# dice2_perf.net
KiCad netlist of a schematic drawn in EAGLE
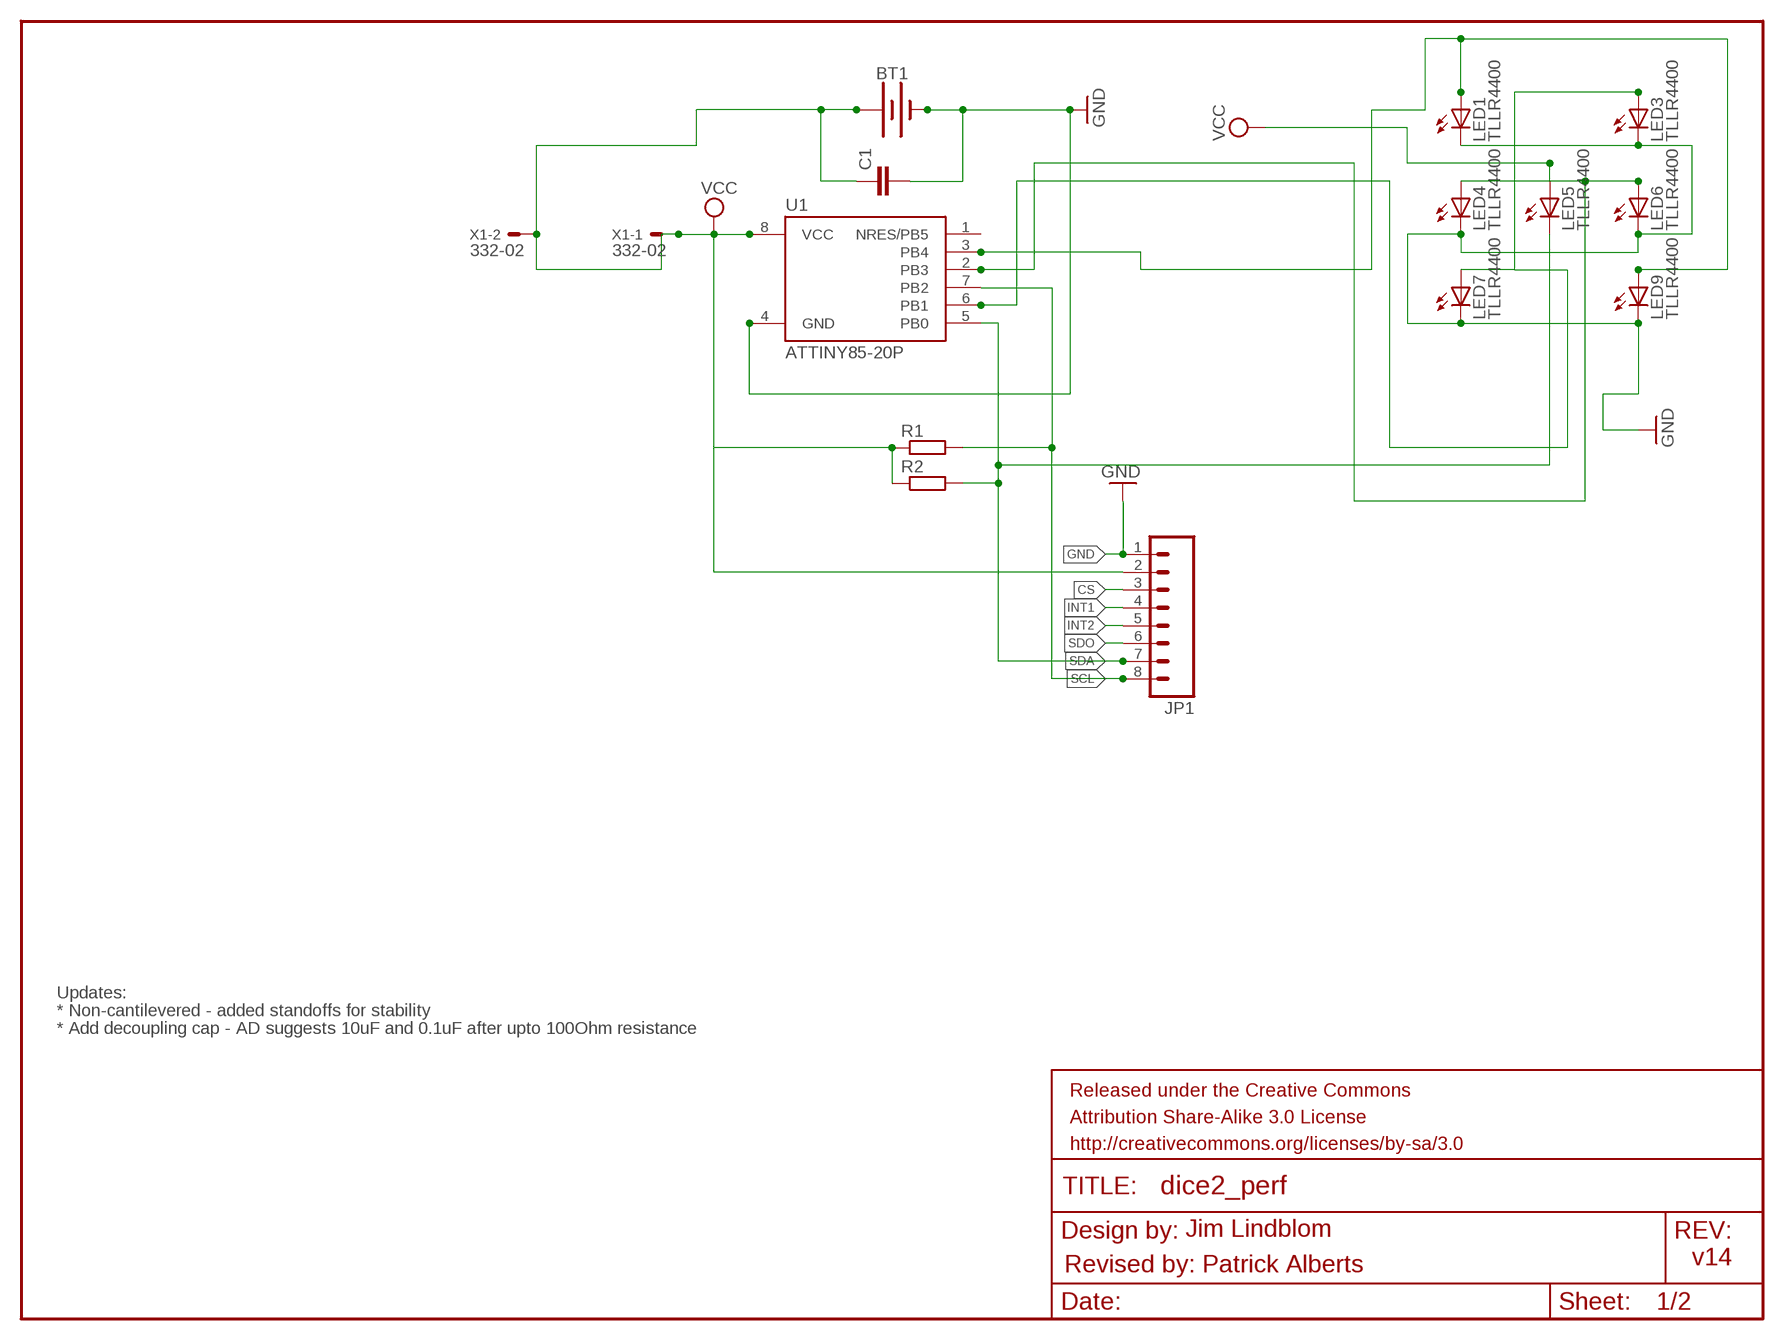
[diagram p0: schematic, sheet 1]

(export (version "E")
  (design (tool "Eeschema 10.0.6"))
  (components
    (comp (ref "BT1")
      (value "BATTERY-20MM_PTH")
      (footprint "eagle-import:BATTCOM_20MM_PTH")
      (libsource (lib "eagle-import") (part "BATTERY-20MM_PTH"))
    )
    (comp (ref "C1")
      (value "C-EU025-024X044")
      (footprint "eagle-import:C025-024X044")
      (libsource (lib "eagle-import") (part "C-EU025-024X044"))
    )
    (comp (ref "JP1")
      (value "M08")
      (footprint "eagle-import:1X08")
      (libsource (lib "eagle-import") (part "M08"))
    )
    (comp (ref "LED1")
      (value "TLLR4400")
      (footprint "eagle-import:LED3MM")
      (fields (field (name "MF") "VISHAY SEMICONDUCTOR"))
      (libsource (lib "eagle-import") (part "TLLR4400"))
    )
    (comp (ref "LED3")
      (value "TLLR4400")
      (footprint "eagle-import:LED3MM")
      (fields (field (name "MF") "VISHAY SEMICONDUCTOR"))
      (libsource (lib "eagle-import") (part "TLLR4400"))
    )
    (comp (ref "LED4")
      (value "TLLR4400")
      (footprint "eagle-import:LED3MM")
      (fields (field (name "MF") "VISHAY SEMICONDUCTOR"))
      (libsource (lib "eagle-import") (part "TLLR4400"))
    )
    (comp (ref "LED5")
      (value "TLLR4400")
      (footprint "eagle-import:LED3MM")
      (fields (field (name "MF") "VISHAY SEMICONDUCTOR"))
      (libsource (lib "eagle-import") (part "TLLR4400"))
    )
    (comp (ref "LED6")
      (value "TLLR4400")
      (footprint "eagle-import:LED3MM")
      (fields (field (name "MF") "VISHAY SEMICONDUCTOR"))
      (libsource (lib "eagle-import") (part "TLLR4400"))
    )
    (comp (ref "LED7")
      (value "TLLR4400")
      (footprint "eagle-import:LED3MM")
      (fields (field (name "MF") "VISHAY SEMICONDUCTOR"))
      (libsource (lib "eagle-import") (part "TLLR4400"))
    )
    (comp (ref "LED9")
      (value "TLLR4400")
      (footprint "eagle-import:LED3MM")
      (fields (field (name "MF") "VISHAY SEMICONDUCTOR"))
      (libsource (lib "eagle-import") (part "TLLR4400"))
    )
    (comp (ref "R1")
      (value "R-EU_0207/12")
      (footprint "eagle-import:0207_12")
      (libsource (lib "eagle-import") (part "R-EU_0207/12"))
    )
    (comp (ref "R2")
      (value "R-EU_0207/2V")
      (footprint "eagle-import:0207_2V")
      (libsource (lib "eagle-import") (part "R-EU_0207/2V"))
    )
    (comp (ref "U1")
      (value "ATTINY85-20P")
      (footprint "eagle-import:PDIP08_300MIL")
      (libsource (lib "eagle-import") (part "ATTINY85P-20"))
    )
    (comp (ref "X1")
      (value "332-02")
      (footprint "eagle-import:332-02")
      (libsource (lib "eagle-import") (part "332-02"))
    )
  )
  (nets
    (net (code "1") (name "CS") (class "Default")
      (node (ref "JP1") (pin "3") (pinfunction "3_3") (pintype "passive"))
    )
    (net (code "2") (name "GND") (class "Default")
      (node (ref "BT1") (pin "2") (pinfunction "-_2") (pintype "power_in"))
      (node (ref "C1") (pin "2") (pinfunction "2_2") (pintype "passive"))
      (node (ref "JP1") (pin "1") (pinfunction "1_1") (pintype "passive"))
      (node (ref "LED1") (pin "K") (pinfunction "C_K") (pintype "passive"))
      (node (ref "LED3") (pin "K") (pinfunction "C_K") (pintype "passive"))
      (node (ref "LED4") (pin "K") (pinfunction "C_K") (pintype "passive"))
      (node (ref "LED6") (pin "K") (pinfunction "C_K") (pintype "passive"))
      (node (ref "LED7") (pin "K") (pinfunction "C_K") (pintype "passive"))
      (node (ref "LED9") (pin "K") (pinfunction "C_K") (pintype "passive"))
      (node (ref "U1") (pin "4") (pinfunction "GND_4") (pintype "power_in"))
    )
    (net (code "3") (name "INT1") (class "Default")
      (node (ref "JP1") (pin "4") (pinfunction "4_4") (pintype "passive"))
    )
    (net (code "4") (name "INT2") (class "Default")
      (node (ref "JP1") (pin "5") (pinfunction "5_5") (pintype "passive"))
    )
    (net (code "5") (name "Net-(U1-PB1)") (class "Default")
      (node (ref "LED3") (pin "A") (pinfunction "A_A") (pintype "passive"))
      (node (ref "LED7") (pin "A") (pinfunction "A_A") (pintype "passive"))
      (node (ref "U1") (pin "6") (pinfunction "PB1_6") (pintype "bidirectional"))
    )
    (net (code "6") (name "Net-(U1-PB3)") (class "Default")
      (node (ref "LED4") (pin "A") (pinfunction "A_A") (pintype "passive"))
      (node (ref "LED6") (pin "A") (pinfunction "A_A") (pintype "passive"))
      (node (ref "U1") (pin "2") (pinfunction "PB3_2") (pintype "bidirectional"))
    )
    (net (code "7") (name "Net-(U1-PB4)") (class "Default")
      (node (ref "LED1") (pin "A") (pinfunction "A_A") (pintype "passive"))
      (node (ref "LED9") (pin "A") (pinfunction "A_A") (pintype "passive"))
      (node (ref "U1") (pin "3") (pinfunction "PB4_3") (pintype "bidirectional"))
    )
    (net (code "8") (name "SCL") (class "Default")
      (node (ref "JP1") (pin "8") (pinfunction "8_8") (pintype "passive"))
      (node (ref "R1") (pin "2") (pinfunction "2_2") (pintype "passive"))
      (node (ref "U1") (pin "7") (pinfunction "PB2_7") (pintype "bidirectional"))
    )
    (net (code "9") (name "SDA") (class "Default")
      (node (ref "JP1") (pin "7") (pinfunction "7_7") (pintype "passive"))
      (node (ref "LED5") (pin "K") (pinfunction "C_K") (pintype "passive"))
      (node (ref "R2") (pin "2") (pinfunction "2_2") (pintype "passive"))
      (node (ref "U1") (pin "5") (pinfunction "PB0_5") (pintype "bidirectional"))
    )
    (net (code "10") (name "SDO") (class "Default")
      (node (ref "JP1") (pin "6") (pinfunction "6_6") (pintype "passive"))
    )
    (net (code "11") (name "VCC") (class "Default")
      (node (ref "BT1") (pin "1") (pinfunction "+_1") (pintype "power_in"))
      (node (ref "C1") (pin "1") (pinfunction "1_1") (pintype "passive"))
      (node (ref "JP1") (pin "2") (pinfunction "2_2") (pintype "passive"))
      (node (ref "LED5") (pin "A") (pinfunction "A_A") (pintype "passive"))
      (node (ref "R1") (pin "1") (pinfunction "1_1") (pintype "passive"))
      (node (ref "R2") (pin "1") (pinfunction "1_1") (pintype "passive"))
      (node (ref "U1") (pin "8") (pinfunction "VCC_8") (pintype "power_in"))
      (node (ref "X1") (pin "1") (pinfunction "S_1") (pintype "passive"))
      (node (ref "X1") (pin "2") (pinfunction "S_2") (pintype "passive"))
    )
    (net (code "12") (name "unconnected-(U1-NRES{slash}PB5-Pad1)") (class "Default")
      (node (ref "U1") (pin "1") (pinfunction "NRES/PB5_1") (pintype "bidirectional"))
    )
  )
)
